# Zio_DC-DC_Booster.net
KiCad netlist of a schematic drawn in EAGLE
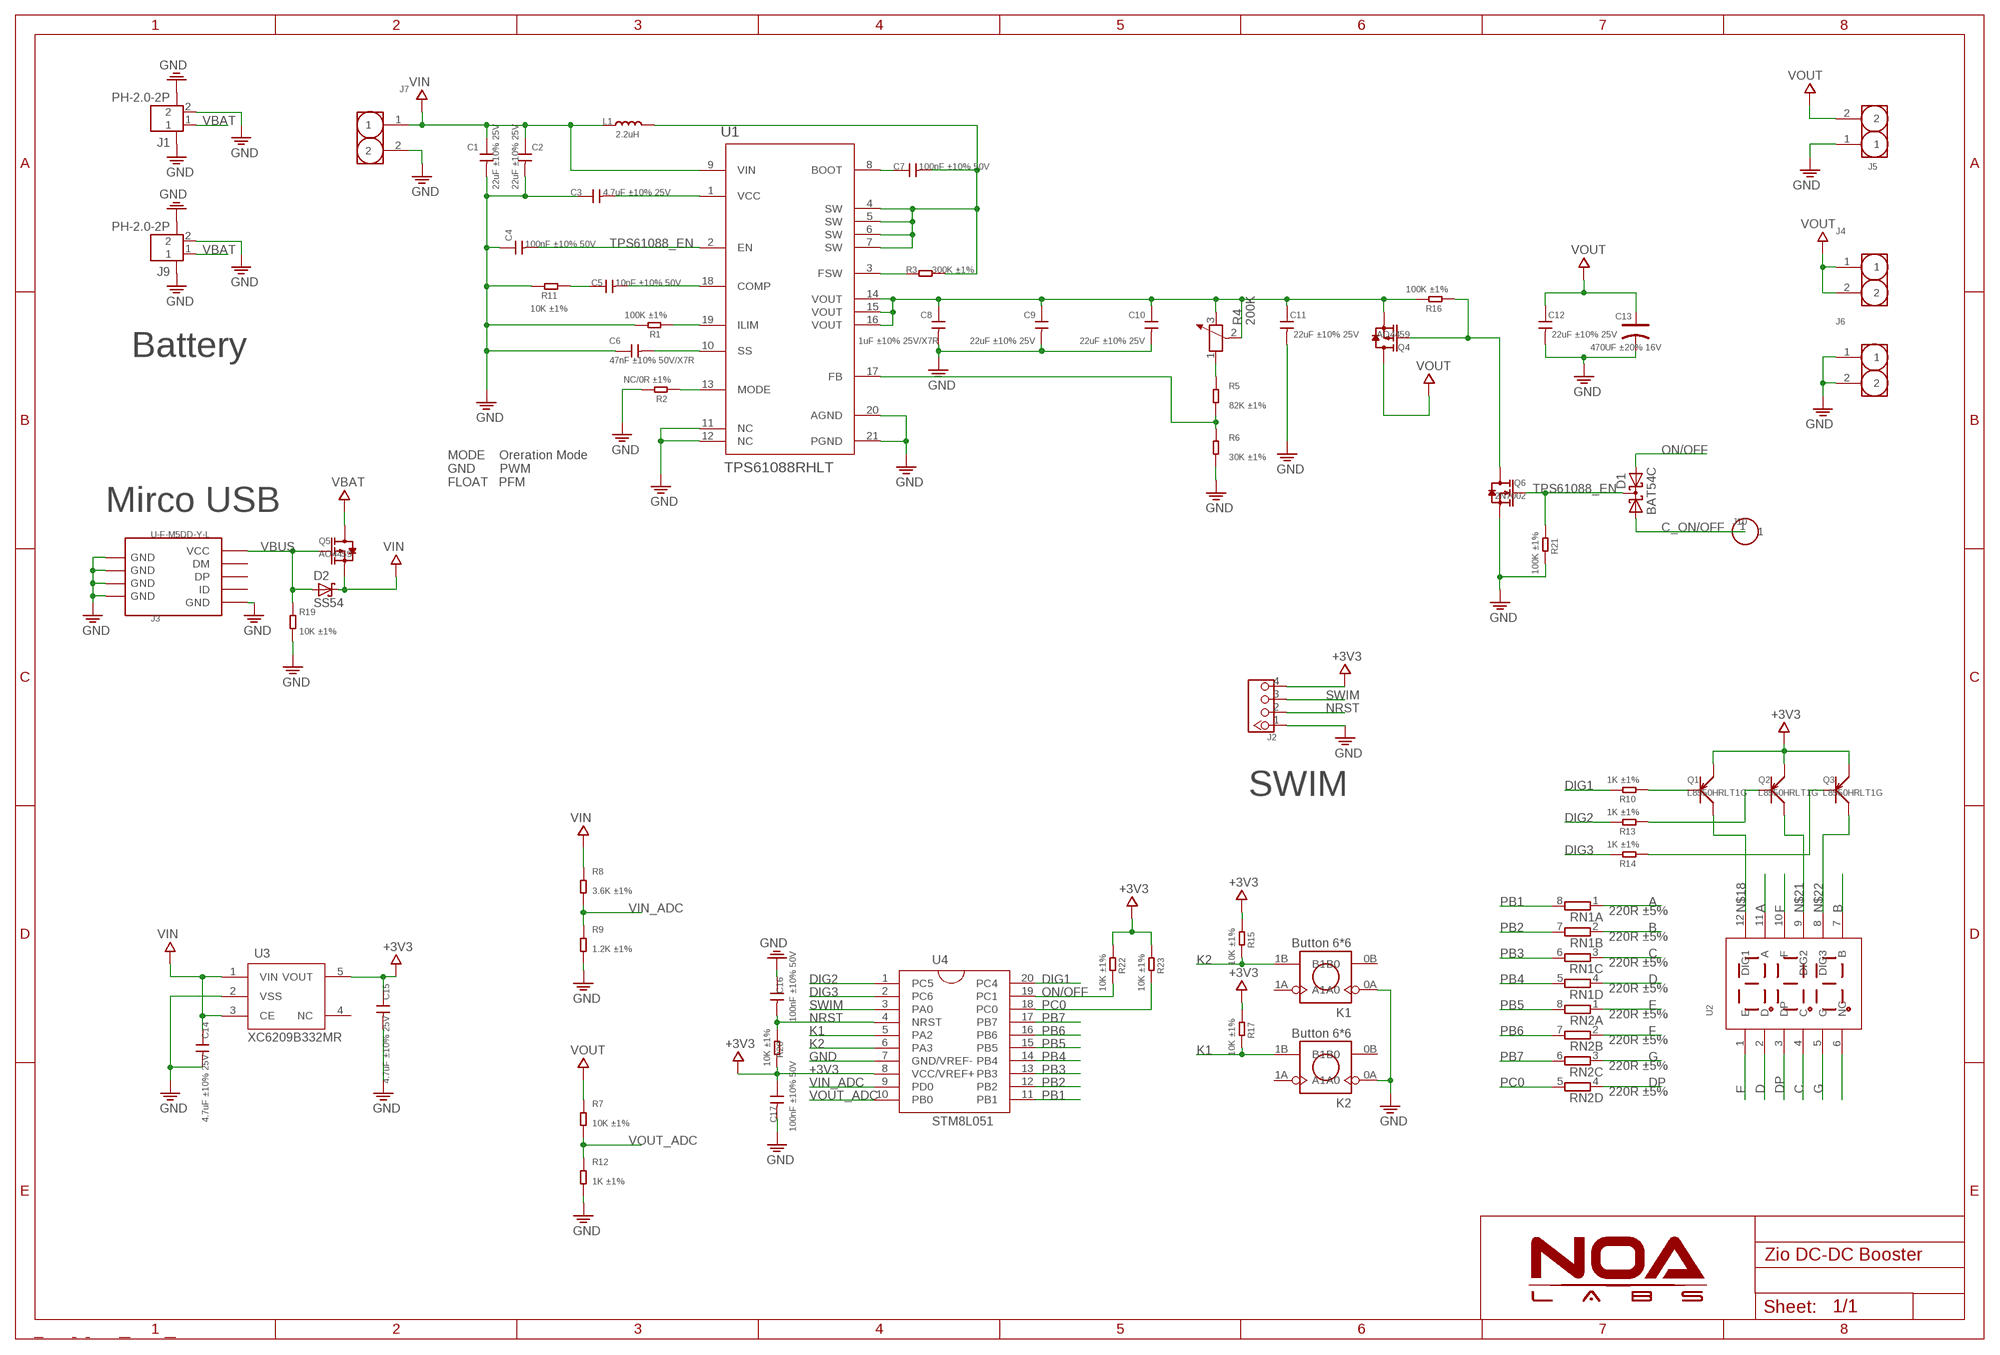
[diagram p0: schematic, sheet 1]

(export (version "E")
  (design (tool "Eeschema 10.0.6"))
  (components
    (comp (ref "C1")
      (value "22uF ±10% 25V")
      (footprint "eagle-import:1206")
      (libsource (lib "eagle-import") (part "C-1206"))
    )
    (comp (ref "C2")
      (value "22uF ±10% 25V")
      (footprint "eagle-import:1206")
      (libsource (lib "eagle-import") (part "C-1206"))
    )
    (comp (ref "C3")
      (value "4.7uF ±10% 25V")
      (footprint "eagle-import:0603")
      (libsource (lib "eagle-import") (part "C-0603"))
    )
    (comp (ref "C4")
      (value "100nF ±10% 50V")
      (footprint "eagle-import:0603")
      (libsource (lib "eagle-import") (part "C-0603"))
    )
    (comp (ref "C5")
      (value "10nF ±10% 50V")
      (footprint "eagle-import:0603")
      (libsource (lib "eagle-import") (part "C-0603"))
    )
    (comp (ref "C6")
      (value "47nF ±10% 50V/X7R")
      (footprint "eagle-import:0603")
      (libsource (lib "eagle-import") (part "C-0603"))
    )
    (comp (ref "C7")
      (value "100nF ±10% 50V")
      (footprint "eagle-import:0603")
      (libsource (lib "eagle-import") (part "C-0603"))
    )
    (comp (ref "C8")
      (value "1uF ±10% 25V/X7R")
      (footprint "eagle-import:0603")
      (libsource (lib "eagle-import") (part "C-0603"))
    )
    (comp (ref "C9")
      (value "22uF ±10% 25V")
      (footprint "eagle-import:1206")
      (libsource (lib "eagle-import") (part "C-1206"))
    )
    (comp (ref "C10")
      (value "22uF ±10% 25V")
      (footprint "eagle-import:1206")
      (libsource (lib "eagle-import") (part "C-1206"))
    )
    (comp (ref "C11")
      (value "22uF ±10% 25V")
      (footprint "eagle-import:1206")
      (libsource (lib "eagle-import") (part "C-1206"))
    )
    (comp (ref "C12")
      (value "22uF ±10% 25V")
      (footprint "eagle-import:1206")
      (libsource (lib "eagle-import") (part "C-1206"))
    )
    (comp (ref "C13")
      (value "470UF ±20% 16V")
      (footprint "eagle-import:ELECTRO-SMD-E-7.8MM")
      (libsource (lib "eagle-import") (part "CAP-ELECTRO-E"))
    )
    (comp (ref "C14")
      (value "4.7uF ±10% 25V")
      (footprint "eagle-import:0603")
      (libsource (lib "eagle-import") (part "C-0603"))
    )
    (comp (ref "C15")
      (value "4.7uF ±10% 25V")
      (footprint "eagle-import:0603")
      (libsource (lib "eagle-import") (part "C-0603"))
    )
    (comp (ref "C16")
      (value "100nF ±10% 50V")
      (footprint "eagle-import:0603")
      (libsource (lib "eagle-import") (part "Discretex_C-0603"))
    )
    (comp (ref "C17")
      (value "100nF ±10% 50V")
      (footprint "eagle-import:0603")
      (libsource (lib "eagle-import") (part "Discretex_C-0603"))
    )
    (comp (ref "D1")
      (value "BAT54C")
      (footprint "eagle-import:SOT23")
      (libsource (lib "eagle-import") (part "BAT54C"))
    )
    (comp (ref "D2")
      (value "SS54")
      (footprint "eagle-import:SMA")
      (libsource (lib "eagle-import") (part "SCHOTTKY"))
    )
    (comp (ref "J1")
      (value "PH-2.0-2P")
      (footprint "eagle-import:PH-2.0-2P")
      (libsource (lib "eagle-import") (part "PH-2.0-2P"))
    )
    (comp (ref "J2")
      (value "HEADER-4P-TEST_3.08_4P")
      (footprint "eagle-import:TEST_3.08_4P")
      (libsource (lib "eagle-import") (part "HEADER-4P-TEST_3.08_4P"))
    )
    (comp (ref "J3")
      (value "U-F-M5DD-Y-L")
      (footprint "eagle-import:MICRO-SMD")
      (libsource (lib "eagle-import") (part "USB-MICROE"))
    )
    (comp (ref "J4")
      (value "HEADER-2P-65/35MIL")
      (footprint "eagle-import:2P-2.54-65_35MIL")
      (libsource (lib "eagle-import") (part "HEADER-2P-65/35MIL"))
    )
    (comp (ref "J5")
      (value "HEADER-2P-SCREW5.0")
      (footprint "eagle-import:2P-SCREW-5.0")
      (libsource (lib "eagle-import") (part "HEADER-2P-SCREW5.0"))
    )
    (comp (ref "J6")
      (value "HEADER-2P-65/35MIL")
      (footprint "eagle-import:2P-2.54-65_35MIL")
      (libsource (lib "eagle-import") (part "HEADER-2P-65/35MIL"))
    )
    (comp (ref "J7")
      (value "HEADER-2P-SCREW5.0")
      (footprint "eagle-import:2P-SCREW-5.0")
      (libsource (lib "eagle-import") (part "HEADER-2P-SCREW5.0"))
    )
    (comp (ref "J9")
      (value "PH-2.0-2P")
      (footprint "eagle-import:PH-2.0-2P")
      (libsource (lib "eagle-import") (part "PH-2.0-2P"))
    )
    (comp (ref "J10")
      (value "HEADER-1P")
      (footprint "eagle-import:1P-40MIL")
      (libsource (lib "eagle-import") (part "HEADER-1P"))
    )
    (comp (ref "K1")
      (value "Button 6*6")
      (footprint "eagle-import:4P-SMD-6X6")
      (libsource (lib "eagle-import") (part "BOTTON-4P-6X6"))
    )
    (comp (ref "K2")
      (value "Button 6*6")
      (footprint "eagle-import:4P-SMD-6X6")
      (libsource (lib "eagle-import") (part "BOTTON-4P-6X6"))
    )
    (comp (ref "L1")
      (value "2.2uH")
      (footprint "eagle-import:L-10.5_11.5")
      (libsource (lib "eagle-import") (part "L-10.511.5"))
    )
    (comp (ref "Q1")
      (value "L8550HRLT1G")
      (footprint "eagle-import:SOT23")
      (libsource (lib "eagle-import") (part "TRANSISTOR-PNP-SOT23"))
    )
    (comp (ref "Q2")
      (value "L8550HRLT1G")
      (footprint "eagle-import:SOT23")
      (libsource (lib "eagle-import") (part "TRANSISTOR-PNP-SOT23"))
    )
    (comp (ref "Q3")
      (value "L8550HRLT1G")
      (footprint "eagle-import:SOT23")
      (libsource (lib "eagle-import") (part "TRANSISTOR-PNP-SOT23"))
    )
    (comp (ref "Q4")
      (value "AO4459")
      (footprint "eagle-import:SOP08")
      (libsource (lib "eagle-import") (part "MOSFET-P-AO4459"))
    )
    (comp (ref "Q5")
      (value "AO4459")
      (footprint "eagle-import:SOP08")
      (libsource (lib "eagle-import") (part "MOSFET-P-AO4459"))
    )
    (comp (ref "Q6")
      (value "2N7002")
      (footprint "eagle-import:SOT23")
      (libsource (lib "eagle-import") (part "MOSFET-N-SOT23"))
    )
    (comp (ref "R1")
      (value "100K ±1%")
      (footprint "eagle-import:0603")
      (libsource (lib "eagle-import") (part "R"))
    )
    (comp (ref "R2")
      (value "NC/0R ±1%")
      (footprint "eagle-import:0402")
      (libsource (lib "eagle-import") (part "R-0402"))
    )
    (comp (ref "R3")
      (value "300K ±1%")
      (footprint "eagle-import:0603")
      (libsource (lib "eagle-import") (part "R"))
    )
    (comp (ref "R4")
      (value "200K")
      (footprint "eagle-import:3P-SQUA-7X6.8")
      (libsource (lib "eagle-import") (part "R-POTENTIOMETER'3362'"))
    )
    (comp (ref "R5")
      (value "82K ±1%")
      (footprint "eagle-import:0603")
      (libsource (lib "eagle-import") (part "R"))
    )
    (comp (ref "R6")
      (value "30K ±1%")
      (footprint "eagle-import:0603")
      (libsource (lib "eagle-import") (part "R"))
    )
    (comp (ref "R7")
      (value "10K ±1%")
      (footprint "eagle-import:0603")
      (libsource (lib "eagle-import") (part "R"))
    )
    (comp (ref "R8")
      (value "3.6K ±1%")
      (footprint "eagle-import:0603")
      (libsource (lib "eagle-import") (part "R"))
    )
    (comp (ref "R9")
      (value "1.2K ±1%")
      (footprint "eagle-import:0603")
      (libsource (lib "eagle-import") (part "R"))
    )
    (comp (ref "R10")
      (value "1K ±1%")
      (footprint "eagle-import:0603")
      (libsource (lib "eagle-import") (part "R"))
    )
    (comp (ref "R11")
      (value "10K ±1%")
      (footprint "eagle-import:0603")
      (libsource (lib "eagle-import") (part "R"))
    )
    (comp (ref "R12")
      (value "1K ±1%")
      (footprint "eagle-import:0603")
      (libsource (lib "eagle-import") (part "R"))
    )
    (comp (ref "R13")
      (value "1K ±1%")
      (footprint "eagle-import:0603")
      (libsource (lib "eagle-import") (part "R"))
    )
    (comp (ref "R14")
      (value "1K ±1%")
      (footprint "eagle-import:0603")
      (libsource (lib "eagle-import") (part "R"))
    )
    (comp (ref "R15")
      (value "10K ±1%")
      (footprint "eagle-import:0603")
      (libsource (lib "eagle-import") (part "R"))
    )
    (comp (ref "R16")
      (value "100K ±1%")
      (footprint "eagle-import:0603")
      (libsource (lib "eagle-import") (part "R"))
    )
    (comp (ref "R17")
      (value "10K ±1%")
      (footprint "eagle-import:0603")
      (libsource (lib "eagle-import") (part "R"))
    )
    (comp (ref "R19")
      (value "10K ±1%")
      (footprint "eagle-import:0603")
      (libsource (lib "eagle-import") (part "R"))
    )
    (comp (ref "R20")
      (value "10K ±1%")
      (footprint "eagle-import:0603")
      (libsource (lib "eagle-import") (part "Discretex_R-0603"))
    )
    (comp (ref "R21")
      (value "100K ±1%")
      (footprint "eagle-import:0603")
      (libsource (lib "eagle-import") (part "R"))
    )
    (comp (ref "R22")
      (value "10K ±1%")
      (footprint "eagle-import:0603")
      (libsource (lib "eagle-import") (part "R"))
    )
    (comp (ref "R23")
      (value "10K ±1%")
      (footprint "eagle-import:0603")
      (libsource (lib "eagle-import") (part "R"))
    )
    (comp (ref "RN1")
      (value "220R ±5%")
      (footprint "eagle-import:RESISTOR-DIL_0603-ARC")
      (libsource (lib "eagle-import") (part "RESISTOR-DIL_4R-N0603-ARC"))
    )
    (comp (ref "RN2")
      (value "220R ±5%")
      (footprint "eagle-import:RESISTOR-DIL_0603-ARC")
      (libsource (lib "eagle-import") (part "RESISTOR-DIL_4R-N0603-ARC"))
    )
    (comp (ref "U1")
      (value "TPS61088RHLT")
      (footprint "eagle-import:IC_RHL0020A")
      (fields (field (name "MANUFACTURER") "Texas Instruments") (field (name "PARTNUMBER") "TPS61088RHLR"))
      (libsource (lib "eagle-import") (part "IC_TPS61088RHLR"))
    )
    (comp (ref "U2")
      (value "SEGMENT_ANODES_3_0.28")
      (footprint "eagle-import:SEGMENT_ANODES_3_0.28")
      (libsource (lib "eagle-import") (part "SEGMENT_ANODES_3_0.28"))
    )
    (comp (ref "U3")
      (value "XC6209B332MR")
      (footprint "eagle-import:SOT23-5")
      (libsource (lib "eagle-import") (part "XC6210"))
    )
    (comp (ref "U4")
      (value "STM8L051")
      (footprint "eagle-import:TSSOP20")
      (libsource (lib "eagle-import") (part "STM8L051"))
    )
  )
  (nets
    (net (code "1") (name "+3V3") (class "Default")
      (node (ref "C15") (pin "1") (pinfunction "1_1") (pintype "passive"))
      (node (ref "C17") (pin "1") (pinfunction "1_1") (pintype "passive"))
      (node (ref "J2") (pin "4") (pinfunction "P$4_4") (pintype "bidirectional"))
      (node (ref "Q1") (pin "2") (pinfunction "E_2") (pintype "passive"))
      (node (ref "Q2") (pin "2") (pinfunction "E_2") (pintype "passive"))
      (node (ref "Q3") (pin "2") (pinfunction "E_2") (pintype "passive"))
      (node (ref "R15") (pin "2") (pinfunction "2_2") (pintype "passive"))
      (node (ref "R17") (pin "2") (pinfunction "2_2") (pintype "passive"))
      (node (ref "R20") (pin "2") (pinfunction "2_2") (pintype "passive"))
      (node (ref "R22") (pin "2") (pinfunction "2_2") (pintype "passive"))
      (node (ref "R23") (pin "2") (pinfunction "2_2") (pintype "passive"))
      (node (ref "U3") (pin "5") (pinfunction "VOUT_5") (pintype "bidirectional"))
      (node (ref "U4") (pin "8") (pinfunction "VCC/VREF+_8") (pintype "bidirectional"))
    )
    (net (code "2") (name "/A") (class "Default")
      (node (ref "RN1") (pin "1") (pinfunction "1_1") (pintype "passive"))
      (node (ref "U2") (pin "11") (pinfunction "A_11") (pintype "bidirectional"))
    )
    (net (code "3") (name "/B") (class "Default")
      (node (ref "RN1") (pin "2") (pinfunction "1_2") (pintype "passive"))
      (node (ref "U2") (pin "7") (pinfunction "B_7") (pintype "bidirectional"))
    )
    (net (code "4") (name "/C") (class "Default")
      (node (ref "RN1") (pin "3") (pinfunction "1_3") (pintype "passive"))
      (node (ref "U2") (pin "4") (pinfunction "C_4") (pintype "bidirectional"))
    )
    (net (code "5") (name "/C_ON{slash}OFF") (class "Default")
      (node (ref "D1") (pin "1") (pinfunction "A1_1") (pintype "passive"))
      (node (ref "J10") (pin "1") (pinfunction "1_1") (pintype "bidirectional"))
    )
    (net (code "6") (name "/D") (class "Default")
      (node (ref "RN1") (pin "4") (pinfunction "1_4") (pintype "passive"))
      (node (ref "U2") (pin "2") (pinfunction "D_2") (pintype "bidirectional"))
    )
    (net (code "7") (name "/DIG1") (class "Default")
      (node (ref "R10") (pin "1") (pinfunction "1_1") (pintype "passive"))
      (node (ref "U4") (pin "20") (pinfunction "PC4_20") (pintype "bidirectional"))
    )
    (net (code "8") (name "/DIG2") (class "Default")
      (node (ref "R13") (pin "1") (pinfunction "1_1") (pintype "passive"))
      (node (ref "U4") (pin "1") (pinfunction "PC5_1") (pintype "bidirectional"))
    )
    (net (code "9") (name "/DIG3") (class "Default")
      (node (ref "R14") (pin "1") (pinfunction "1_1") (pintype "passive"))
      (node (ref "U4") (pin "2") (pinfunction "PC6_2") (pintype "bidirectional"))
    )
    (net (code "10") (name "/DP") (class "Default")
      (node (ref "RN2") (pin "4") (pinfunction "1_4") (pintype "passive"))
      (node (ref "U2") (pin "3") (pinfunction "DP_3") (pintype "bidirectional"))
    )
    (net (code "11") (name "/E") (class "Default")
      (node (ref "RN2") (pin "1") (pinfunction "1_1") (pintype "passive"))
      (node (ref "U2") (pin "1") (pinfunction "E_1") (pintype "bidirectional"))
    )
    (net (code "12") (name "/F") (class "Default")
      (node (ref "RN2") (pin "2") (pinfunction "1_2") (pintype "passive"))
      (node (ref "U2") (pin "10") (pinfunction "F_10") (pintype "bidirectional"))
    )
    (net (code "13") (name "/G") (class "Default")
      (node (ref "RN2") (pin "3") (pinfunction "1_3") (pintype "passive"))
      (node (ref "U2") (pin "5") (pinfunction "G_5") (pintype "bidirectional"))
    )
    (net (code "14") (name "/K1") (class "Default")
      (node (ref "K2") (pin "1B") (pinfunction "B1_1B") (pintype "bidirectional"))
      (node (ref "R17") (pin "1") (pinfunction "1_1") (pintype "passive"))
      (node (ref "U4") (pin "5") (pinfunction "PA2_5") (pintype "bidirectional"))
    )
    (net (code "15") (name "/K2") (class "Default")
      (node (ref "K1") (pin "1B") (pinfunction "B1_1B") (pintype "bidirectional"))
      (node (ref "R15") (pin "1") (pinfunction "1_1") (pintype "passive"))
      (node (ref "U4") (pin "6") (pinfunction "PA3_6") (pintype "bidirectional"))
    )
    (net (code "16") (name "/N$18") (class "Default")
      (node (ref "Q1") (pin "3") (pinfunction "C_3") (pintype "passive"))
      (node (ref "U2") (pin "12") (pinfunction "DIG1_12") (pintype "bidirectional"))
    )
    (net (code "17") (name "/N$21") (class "Default")
      (node (ref "Q2") (pin "3") (pinfunction "C_3") (pintype "passive"))
      (node (ref "U2") (pin "9") (pinfunction "DIG2_9") (pintype "bidirectional"))
    )
    (net (code "18") (name "/N$22") (class "Default")
      (node (ref "Q3") (pin "3") (pinfunction "C_3") (pintype "passive"))
      (node (ref "U2") (pin "8") (pinfunction "DIG3_8") (pintype "bidirectional"))
    )
    (net (code "19") (name "/NRST") (class "Default")
      (node (ref "C16") (pin "2") (pinfunction "2_2") (pintype "passive"))
      (node (ref "J2") (pin "2") (pinfunction "P$2_2") (pintype "bidirectional"))
      (node (ref "R20") (pin "1") (pinfunction "1_1") (pintype "passive"))
      (node (ref "U4") (pin "4") (pinfunction "NRST_4") (pintype "bidirectional"))
    )
    (net (code "20") (name "/ON{slash}OFF") (class "Default")
      (node (ref "D1") (pin "2") (pinfunction "A2_2") (pintype "passive"))
      (node (ref "R22") (pin "1") (pinfunction "1_1") (pintype "passive"))
      (node (ref "U4") (pin "19") (pinfunction "PC1_19") (pintype "bidirectional"))
    )
    (net (code "21") (name "/PB1") (class "Default")
      (node (ref "RN1") (pin "8") (pinfunction "2_8") (pintype "passive"))
      (node (ref "U4") (pin "11") (pinfunction "PB1_11") (pintype "bidirectional"))
    )
    (net (code "22") (name "/PB2") (class "Default")
      (node (ref "RN1") (pin "7") (pinfunction "2_7") (pintype "passive"))
      (node (ref "U4") (pin "12") (pinfunction "PB2_12") (pintype "bidirectional"))
    )
    (net (code "23") (name "/PB3") (class "Default")
      (node (ref "RN1") (pin "6") (pinfunction "2_6") (pintype "passive"))
      (node (ref "U4") (pin "13") (pinfunction "PB3_13") (pintype "bidirectional"))
    )
    (net (code "24") (name "/PB4") (class "Default")
      (node (ref "RN1") (pin "5") (pinfunction "2_5") (pintype "passive"))
      (node (ref "U4") (pin "14") (pinfunction "PB4_14") (pintype "bidirectional"))
    )
    (net (code "25") (name "/PB5") (class "Default")
      (node (ref "RN2") (pin "8") (pinfunction "2_8") (pintype "passive"))
      (node (ref "U4") (pin "15") (pinfunction "PB5_15") (pintype "bidirectional"))
    )
    (net (code "26") (name "/PB6") (class "Default")
      (node (ref "RN2") (pin "7") (pinfunction "2_7") (pintype "passive"))
      (node (ref "U4") (pin "16") (pinfunction "PB6_16") (pintype "bidirectional"))
    )
    (net (code "27") (name "/PB7") (class "Default")
      (node (ref "RN2") (pin "6") (pinfunction "2_6") (pintype "passive"))
      (node (ref "U4") (pin "17") (pinfunction "PB7_17") (pintype "bidirectional"))
    )
    (net (code "28") (name "/PC0") (class "Default")
      (node (ref "R23") (pin "1") (pinfunction "1_1") (pintype "passive"))
      (node (ref "RN2") (pin "5") (pinfunction "2_5") (pintype "passive"))
      (node (ref "U4") (pin "18") (pinfunction "PC0_18") (pintype "bidirectional"))
    )
    (net (code "29") (name "/SWIM") (class "Default")
      (node (ref "J2") (pin "3") (pinfunction "P$3_3") (pintype "bidirectional"))
      (node (ref "U4") (pin "3") (pinfunction "PA0_3") (pintype "bidirectional"))
    )
    (net (code "30") (name "/TPS61088_EN") (class "Default")
      (node (ref "C4") (pin "2") (pinfunction "2_2") (pintype "passive"))
      (node (ref "D1") (pin "3") (pinfunction "CC_3") (pintype "passive"))
      (node (ref "Q6") (pin "1") (pinfunction "G_1") (pintype "passive"))
      (node (ref "R21") (pin "2") (pinfunction "2_2") (pintype "passive"))
      (node (ref "U1") (pin "2") (pinfunction "EN_2") (pintype "input"))
    )
    (net (code "31") (name "/VBUS") (class "Default")
      (node (ref "D2") (pin "P$2") (pinfunction "A_P$2") (pintype "passive"))
      (node (ref "J3") (pin "VBUS") (pinfunction "VCC_VBUS") (pintype "bidirectional"))
      (node (ref "Q5") (pin "4") (pinfunction "G_4") (pintype "passive"))
      (node (ref "R19") (pin "1") (pinfunction "1_1") (pintype "passive"))
    )
    (net (code "32") (name "/VIN_ADC") (class "Default")
      (node (ref "R8") (pin "1") (pinfunction "1_1") (pintype "passive"))
      (node (ref "R9") (pin "2") (pinfunction "2_2") (pintype "passive"))
      (node (ref "U4") (pin "9") (pinfunction "PD0_9") (pintype "bidirectional"))
    )
    (net (code "33") (name "/VOUT_ADC") (class "Default")
      (node (ref "R12") (pin "2") (pinfunction "2_2") (pintype "passive"))
      (node (ref "R7") (pin "1") (pinfunction "1_1") (pintype "passive"))
      (node (ref "U4") (pin "10") (pinfunction "PB0_10") (pintype "bidirectional"))
    )
    (net (code "34") (name "GND") (class "Default")
      (node (ref "C1") (pin "2") (pinfunction "2_2") (pintype "passive"))
      (node (ref "C10") (pin "2") (pinfunction "2_2") (pintype "passive"))
      (node (ref "C11") (pin "2") (pinfunction "2_2") (pintype "passive"))
      (node (ref "C12") (pin "2") (pinfunction "2_2") (pintype "passive"))
      (node (ref "C13") (pin "-") (pinfunction "-_-") (pintype "passive"))
      (node (ref "C14") (pin "2") (pinfunction "2_2") (pintype "passive"))
      (node (ref "C15") (pin "2") (pinfunction "2_2") (pintype "passive"))
      (node (ref "C16") (pin "1") (pinfunction "1_1") (pintype "passive"))
      (node (ref "C17") (pin "2") (pinfunction "2_2") (pintype "passive"))
      (node (ref "C2") (pin "2") (pinfunction "2_2") (pintype "passive"))
      (node (ref "C3") (pin "1") (pinfunction "1_1") (pintype "passive"))
      (node (ref "C4") (pin "1") (pinfunction "1_1") (pintype "passive"))
      (node (ref "C6") (pin "1") (pinfunction "1_1") (pintype "passive"))
      (node (ref "C8") (pin "2") (pinfunction "2_2") (pintype "passive"))
      (node (ref "C9") (pin "2") (pinfunction "2_2") (pintype "passive"))
      (node (ref "J1") (pin "2") (pinfunction "2_2") (pintype "bidirectional"))
      (node (ref "J1") (pin "7") (pinfunction "3_7") (pintype "bidirectional"))
      (node (ref "J1") (pin "8") (pinfunction "4_8") (pintype "bidirectional"))
      (node (ref "J2") (pin "1") (pinfunction "P$1_1") (pintype "bidirectional"))
      (node (ref "J3") (pin "GND") (pinfunction "GND_GND") (pintype "bidirectional"))
      (node (ref "J3") (pin "S1") (pinfunction "GND_S1") (pintype "bidirectional"))
      (node (ref "J3") (pin "S1@1") (pinfunction "GND_S1@1") (pintype "bidirectional"))
      (node (ref "J3") (pin "S1@2") (pinfunction "GND_S1@2") (pintype "bidirectional"))
      (node (ref "J3") (pin "S2") (pinfunction "GND_S2") (pintype "bidirectional"))
      (node (ref "J3") (pin "S2@1") (pinfunction "GND_S2@1") (pintype "bidirectional"))
      (node (ref "J3") (pin "S2@2") (pinfunction "GND_S2@2") (pintype "bidirectional"))
      (node (ref "J3") (pin "S3") (pinfunction "GND_S3") (pintype "bidirectional"))
      (node (ref "J3") (pin "S3@1") (pinfunction "GND_S3@1") (pintype "bidirectional"))
      (node (ref "J3") (pin "S3@2") (pinfunction "GND_S3@2") (pintype "bidirectional"))
      (node (ref "J3") (pin "S4") (pinfunction "GND_S4") (pintype "bidirectional"))
      (node (ref "J3") (pin "S4@1") (pinfunction "GND_S4@1") (pintype "bidirectional"))
      (node (ref "J3") (pin "S4@2") (pinfunction "GND_S4@2") (pintype "bidirectional"))
      (node (ref "J5") (pin "1") (pinfunction "1_1") (pintype "bidirectional"))
      (node (ref "J6") (pin "1") (pinfunction "1_1") (pintype "bidirectional"))
      (node (ref "J6") (pin "2") (pinfunction "2_2") (pintype "bidirectional"))
      (node (ref "J7") (pin "2") (pinfunction "2_2") (pintype "bidirectional"))
      (node (ref "J9") (pin "2") (pinfunction "2_2") (pintype "bidirectional"))
      (node (ref "J9") (pin "7") (pinfunction "3_7") (pintype "bidirectional"))
      (node (ref "J9") (pin "8") (pinfunction "4_8") (pintype "bidirectional"))
      (node (ref "K1") (pin "0A") (pinfunction "A0_0A") (pintype "bidirectional"))
      (node (ref "K2") (pin "0A") (pinfunction "A0_0A") (pintype "bidirectional"))
      (node (ref "Q6") (pin "2") (pinfunction "S_2") (pintype "passive"))
      (node (ref "R1") (pin "1") (pinfunction "1_1") (pintype "passive"))
      (node (ref "R11") (pin "1") (pinfunction "1_1") (pintype "passive"))
      (node (ref "R12") (pin "1") (pinfunction "1_1") (pintype "passive"))
      (node (ref "R19") (pin "2") (pinfunction "2_2") (pintype "passive"))
      (node (ref "R2") (pin "1") (pinfunction "1_1") (pintype "passive"))
      (node (ref "R21") (pin "1") (pinfunction "1_1") (pintype "passive"))
      (node (ref "R6") (pin "2") (pinfunction "2_2") (pintype "passive"))
      (node (ref "R9") (pin "1") (pinfunction "1_1") (pintype "passive"))
      (node (ref "U1") (pin "11") (pinfunction "NC_11") (pintype "passive"))
      (node (ref "U1") (pin "12") (pinfunction "NC_12") (pintype "passive"))
      (node (ref "U1") (pin "20") (pinfunction "AGND_20") (pintype "power_in"))
      (node (ref "U1") (pin "21") (pinfunction "PGND_21") (pintype "power_in"))
      (node (ref "U3") (pin "2") (pinfunction "VSS_2") (pintype "bidirectional"))
      (node (ref "U4") (pin "7") (pinfunction "GND/VREF-_7") (pintype "bidirectional"))
    )
    (net (code "35") (name "Net-(C5-Pad1)") (class "Default")
      (node (ref "C5") (pin "1") (pinfunction "1_1") (pintype "passive"))
      (node (ref "R11") (pin "2") (pinfunction "2_2") (pintype "passive"))
    )
    (net (code "36") (name "Net-(C7-Pad2)") (class "Default")
      (node (ref "C7") (pin "2") (pinfunction "2_2") (pintype "passive"))
      (node (ref "L1") (pin "2") (pinfunction "2_2") (pintype "passive"))
      (node (ref "R3") (pin "2") (pinfunction "2_2") (pintype "passive"))
      (node (ref "U1") (pin "4") (pinfunction "SW_4") (pintype "power_in"))
      (node (ref "U1") (pin "5") (pinfunction "SW_5") (pintype "power_in"))
      (node (ref "U1") (pin "6") (pinfunction "SW_6") (pintype "power_in"))
      (node (ref "U1") (pin "7") (pinfunction "SW_7") (pintype "power_in"))
    )
    (net (code "37") (name "Net-(C10-Pad1)") (class "Default")
      (node (ref "C10") (pin "1") (pinfunction "1_1") (pintype "passive"))
      (node (ref "C11") (pin "1") (pinfunction "1_1") (pintype "passive"))
      (node (ref "C8") (pin "1") (pinfunction "1_1") (pintype "passive"))
      (node (ref "C9") (pin "1") (pinfunction "1_1") (pintype "passive"))
      (node (ref "Q4") (pin "1") (pinfunction "S_1") (pintype "passive"))
      (node (ref "Q4") (pin "2") (pinfunction "S_2") (pintype "passive"))
      (node (ref "Q4") (pin "3") (pinfunction "S_3") (pintype "passive"))
      (node (ref "R16") (pin "1") (pinfunction "1_1") (pintype "passive"))
      (node (ref "R4") (pin "2") (pinfunction "2_2") (pintype "passive"))
      (node (ref "R4") (pin "3") (pinfunction "3_3") (pintype "passive"))
      (node (ref "U1") (pin "14") (pinfunction "VOUT_14") (pintype "power_in"))
      (node (ref "U1") (pin "15") (pinfunction "VOUT_15") (pintype "power_in"))
      (node (ref "U1") (pin "16") (pinfunction "VOUT_16") (pintype "power_in"))
    )
    (net (code "38") (name "Net-(Q1-B)") (class "Default")
      (node (ref "Q1") (pin "1") (pinfunction "B_1") (pintype "passive"))
      (node (ref "R10") (pin "2") (pinfunction "2_2") (pintype "passive"))
    )
    (net (code "39") (name "Net-(Q2-B)") (class "Default")
      (node (ref "Q2") (pin "1") (pinfunction "B_1") (pintype "passive"))
      (node (ref "R13") (pin "2") (pinfunction "2_2") (pintype "passive"))
    )
    (net (code "40") (name "Net-(Q3-B)") (class "Default")
      (node (ref "Q3") (pin "1") (pinfunction "B_1") (pintype "passive"))
      (node (ref "R14") (pin "2") (pinfunction "2_2") (pintype "passive"))
    )
    (net (code "41") (name "Net-(Q4-G)") (class "Default")
      (node (ref "Q4") (pin "4") (pinfunction "G_4") (pintype "passive"))
      (node (ref "Q6") (pin "3") (pinfunction "D_3") (pintype "passive"))
      (node (ref "R16") (pin "2") (pinfunction "2_2") (pintype "passive"))
    )
    (net (code "42") (name "Net-(R4-Pad1)") (class "Default")
      (node (ref "R4") (pin "1") (pinfunction "1_1") (pintype "passive"))
      (node (ref "R5") (pin "1") (pinfunction "1_1") (pintype "passive"))
    )
    (net (code "43") (name "Net-(U1-BOOT)") (class "Default")
      (node (ref "C7") (pin "1") (pinfunction "1_1") (pintype "passive"))
      (node (ref "U1") (pin "8") (pinfunction "BOOT_8") (pintype "power_in"))
    )
    (net (code "44") (name "Net-(U1-COMP)") (class "Default")
      (node (ref "C5") (pin "2") (pinfunction "2_2") (pintype "passive"))
      (node (ref "U1") (pin "18") (pinfunction "COMP_18") (pintype "output"))
    )
    (net (code "45") (name "Net-(U1-FB)") (class "Default")
      (node (ref "R5") (pin "2") (pinfunction "2_2") (pintype "passive"))
      (node (ref "R6") (pin "1") (pinfunction "1_1") (pintype "passive"))
      (node (ref "U1") (pin "17") (pinfunction "FB_17") (pintype "input"))
    )
    (net (code "46") (name "Net-(U1-FSW)") (class "Default")
      (node (ref "R3") (pin "1") (pinfunction "1_1") (pintype "passive"))
      (node (ref "U1") (pin "3") (pinfunction "FSW_3") (pintype "input"))
    )
    (net (code "47") (name "Net-(U1-ILIM)") (class "Default")
      (node (ref "R1") (pin "2") (pinfunction "2_2") (pintype "passive"))
      (node (ref "U1") (pin "19") (pinfunction "ILIM_19") (pintype "input"))
    )
    (net (code "48") (name "Net-(U1-MODE)") (class "Default")
      (node (ref "R2") (pin "2") (pinfunction "2_2") (pintype "passive"))
      (node (ref "U1") (pin "13") (pinfunction "MODE_13") (pintype "input"))
    )
    (net (code "49") (name "Net-(U1-SS)") (class "Default")
      (node (ref "C6") (pin "2") (pinfunction "2_2") (pintype "passive"))
      (node (ref "U1") (pin "10") (pinfunction "SS_10") (pintype "input"))
    )
    (net (code "50") (name "Net-(U1-VCC)") (class "Default")
      (node (ref "C3") (pin "2") (pinfunction "2_2") (pintype "passive"))
      (node (ref "U1") (pin "1") (pinfunction "VCC_1") (pintype "power_in"))
    )
    (net (code "51") (name "VBAT") (class "Default")
      (node (ref "J1") (pin "1") (pinfunction "1_1") (pintype "bidirectional"))
      (node (ref "J9") (pin "1") (pinfunction "1_1") (pintype "bidirectional"))
      (node (ref "Q5") (pin "5") (pinfunction "D_5") (pintype "passive"))
      (node (ref "Q5") (pin "6") (pinfunction "D_6") (pintype "passive"))
      (node (ref "Q5") (pin "7") (pinfunction "D_7") (pintype "passive"))
      (node (ref "Q5") (pin "8") (pinfunction "D_8") (pintype "passive"))
    )
    (net (code "52") (name "VIN") (class "Default")
      (node (ref "C1") (pin "1") (pinfunction "1_1") (pintype "passive"))
      (node (ref "C14") (pin "1") (pinfunction "1_1") (pintype "passive"))
      (node (ref "C2") (pin "1") (pinfunction "1_1") (pintype "passive"))
      (node (ref "D2") (pin "P$1") (pinfunction "C_P$1") (pintype "passive"))
      (node (ref "J7") (pin "1") (pinfunction "1_1") (pintype "bidirectional"))
      (node (ref "L1") (pin "1") (pinfunction "1_1") (pintype "passive"))
      (node (ref "Q5") (pin "1") (pinfunction "S_1") (pintype "passive"))
      (node (ref "Q5") (pin "2") (pinfunction "S_2") (pintype "passive"))
      (node (ref "Q5") (pin "3") (pinfunction "S_3") (pintype "passive"))
      (node (ref "R8") (pin "2") (pinfunction "2_2") (pintype "passive"))
      (node (ref "U1") (pin "9") (pinfunction "VIN_9") (pintype "power_in"))
      (node (ref "U3") (pin "1") (pinfunction "VIN_1") (pintype "bidirectional"))
      (node (ref "U3") (pin "3") (pinfunction "CE_3") (pintype "bidirectional"))
    )
    (net (code "53") (name "VOUT") (class "Default")
      (node (ref "C12") (pin "1") (pinfunction "1_1") (pintype "passive"))
      (node (ref "C13") (pin "+") (pinfunction "+_+") (pintype "passive"))
      (node (ref "J4") (pin "1") (pinfunction "1_1") (pintype "bidirectional"))
      (node (ref "J4") (pin "2") (pinfunction "2_2") (pintype "bidirectional"))
      (node (ref "J5") (pin "2") (pinfunction "2_2") (pintype "bidirectional"))
      (node (ref "Q4") (pin "5") (pinfunction "D_5") (pintype "passive"))
      (node (ref "Q4") (pin "6") (pinfunction "D_6") (pintype "passive"))
      (node (ref "Q4") (pin "7") (pinfunction "D_7") (pintype "passive"))
      (node (ref "Q4") (pin "8") (pinfunction "D_8") (pintype "passive"))
      (node (ref "R7") (pin "2") (pinfunction "2_2") (pintype "passive"))
    )
    (net (code "54") (name "unconnected-(J3-DM-PadD-)") (class "Default")
      (node (ref "J3") (pin "D-") (pinfunction "DM_D-") (pintype "bidirectional"))
    )
    (net (code "55") (name "unconnected-(J3-DP-PadD+)") (class "Default")
      (node (ref "J3") (pin "D+") (pinfunction "DP_D+") (pintype "bidirectional"))
    )
    (net (code "56") (name "unconnected-(J3-PadID)") (class "Default")
      (node (ref "J3") (pin "ID") (pinfunction "ID_ID") (pintype "bidirectional"))
    )
    (net (code "57") (name "unconnected-(K1-A1-Pad1A)") (class "Default")
      (node (ref "K1") (pin "1A") (pinfunction "A1_1A") (pintype "bidirectional"))
    )
    (net (code "58") (name "unconnected-(K1-B0-Pad0B)") (class "Default")
      (node (ref "K1") (pin "0B") (pinfunction "B0_0B") (pintype "bidirectional"))
    )
    (net (code "59") (name "unconnected-(K2-A1-Pad1A)") (class "Default")
      (node (ref "K2") (pin "1A") (pinfunction "A1_1A") (pintype "bidirectional"))
    )
    (net (code "60") (name "unconnected-(K2-B0-Pad0B)") (class "Default")
      (node (ref "K2") (pin "0B") (pinfunction "B0_0B") (pintype "bidirectional"))
    )
    (net (code "61") (name "unconnected-(U2-NC-Pad6)") (class "Default")
      (node (ref "U2") (pin "6") (pinfunction "NC_6") (pintype "bidirectional"))
    )
    (net (code "62") (name "unconnected-(U3-NC-Pad4)") (class "Default")
      (node (ref "U3") (pin "4") (pinfunction "NC_4") (pintype "bidirectional"))
    )
  )
)
